# QUES_-1_2.net
KiCad netlist of a schematic drawn in EAGLE
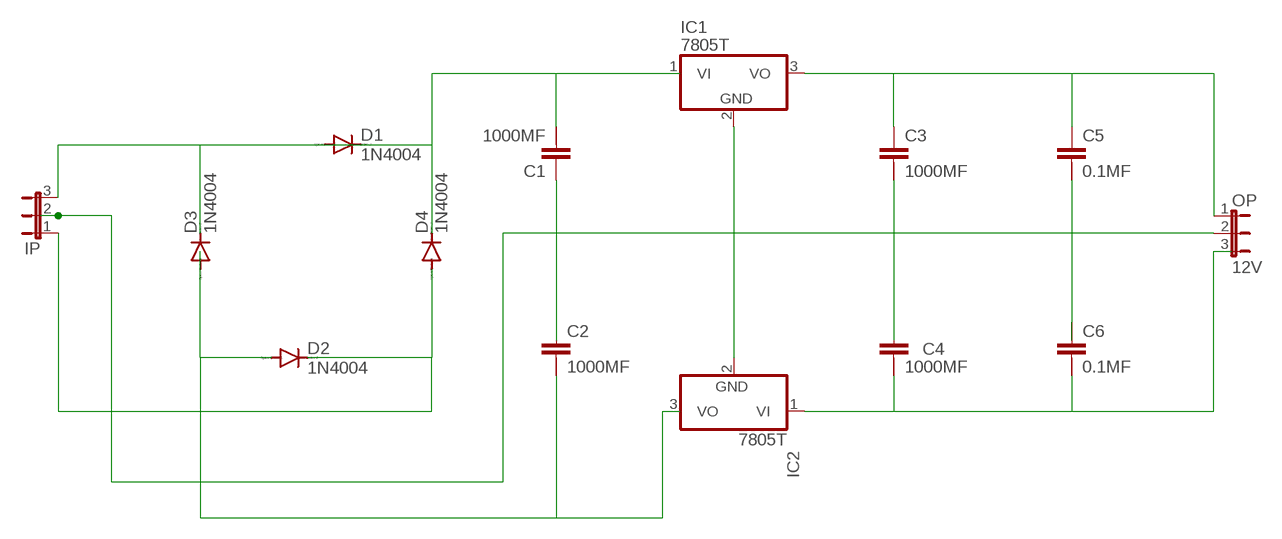
[diagram p0: schematic, sheet 1]

(export (version "E")
  (design (tool "Eeschema 10.0.6"))
  (components
    (comp (ref "C1")
      (value "1000MF")
      (footprint "eagle-import:C2.5_5-2")
      (libsource (lib "eagle-import") (part "C-2.5-5/2"))
    )
    (comp (ref "C2")
      (value "1000MF")
      (footprint "eagle-import:C2.5_5-2")
      (libsource (lib "eagle-import") (part "C-2.5-5/2"))
    )
    (comp (ref "C3")
      (value "1000MF")
      (footprint "eagle-import:C2.5_5-2")
      (libsource (lib "eagle-import") (part "C-2.5-5/2"))
    )
    (comp (ref "C4")
      (value "1000MF")
      (footprint "eagle-import:C2.5_5-2")
      (libsource (lib "eagle-import") (part "C-2.5-5/2"))
    )
    (comp (ref "C5")
      (value "0.1MF")
      (footprint "eagle-import:C2.5_5-2")
      (libsource (lib "eagle-import") (part "C-2.5-5/2"))
    )
    (comp (ref "C6")
      (value "0.1MF")
      (footprint "eagle-import:C2.5_5-2")
      (libsource (lib "eagle-import") (part "C-2.5-5/2"))
    )
    (comp (ref "D1")
      (value "1N4004")
      (footprint "eagle-import:DO41-10")
      (libsource (lib "eagle-import") (part "1N4004"))
    )
    (comp (ref "D2")
      (value "1N4004")
      (footprint "eagle-import:DO41-10")
      (libsource (lib "eagle-import") (part "1N4004"))
    )
    (comp (ref "D3")
      (value "1N4004")
      (footprint "eagle-import:DO41-10")
      (libsource (lib "eagle-import") (part "1N4004"))
    )
    (comp (ref "D4")
      (value "1N4004")
      (footprint "eagle-import:DO41-10")
      (libsource (lib "eagle-import") (part "1N4004"))
    )
    (comp (ref "IC1")
      (value "7805T")
      (footprint "eagle-import:TO220H")
      (libsource (lib "eagle-import") (part "78T05"))
    )
    (comp (ref "IC2")
      (value "7805T")
      (footprint "eagle-import:TO220H")
      (libsource (lib "eagle-import") (part "78T05"))
    )
    (comp (ref "IP")
      (value "JP2E")
      (footprint "eagle-import:JP2")
      (libsource (lib "eagle-import") (part "JP2E"))
    )
    (comp (ref "OP")
      (value "12V")
      (footprint "eagle-import:JP2")
      (libsource (lib "eagle-import") (part "JP2E"))
    )
  )
  (nets
    (net (code "1") (name "Net-(C1-Pad1)") (class "Default")
      (node (ref "C1") (pin "1") (pinfunction "1_1") (pintype "passive"))
      (node (ref "C2") (pin "1") (pinfunction "1_1") (pintype "passive"))
    )
    (net (code "2") (name "Net-(C3-Pad2)") (class "Default")
      (node (ref "C3") (pin "2") (pinfunction "2_2") (pintype "passive"))
      (node (ref "C4") (pin "1") (pinfunction "1_1") (pintype "passive"))
    )
    (net (code "3") (name "Net-(C5-Pad2)") (class "Default")
      (node (ref "C5") (pin "2") (pinfunction "2_2") (pintype "passive"))
      (node (ref "C6") (pin "1") (pinfunction "1_1") (pintype "passive"))
    )
    (net (code "4") (name "Net-(D2-PadC)") (class "Default")
      (node (ref "D2") (pin "C") (pinfunction "C_C") (pintype "passive"))
      (node (ref "D4") (pin "A") (pinfunction "A_A") (pintype "passive"))
      (node (ref "IP") (pin "1") (pinfunction "1_1") (pintype "passive"))
    )
    (net (code "5") (name "Net-(IC1-GND)") (class "Default")
      (node (ref "IC1") (pin "2") (pinfunction "GND_2") (pintype "passive"))
      (node (ref "IC2") (pin "2") (pinfunction "GND_2") (pintype "passive"))
    )
    (net (code "6") (name "Net-(IC1-VI)") (class "Default")
      (node (ref "C1") (pin "2") (pinfunction "2_2") (pintype "passive"))
      (node (ref "D1") (pin "A") (pinfunction "A_A") (pintype "passive"))
      (node (ref "D1") (pin "C") (pinfunction "C_C") (pintype "passive"))
      (node (ref "D3") (pin "C") (pinfunction "C_C") (pintype "passive"))
      (node (ref "D4") (pin "C") (pinfunction "C_C") (pintype "passive"))
      (node (ref "IC1") (pin "1") (pinfunction "VI_1") (pintype "input"))
      (node (ref "IP") (pin "3") (pinfunction "3_3") (pintype "passive"))
    )
    (net (code "7") (name "Net-(IC1-VO)") (class "Default")
      (node (ref "C3") (pin "1") (pinfunction "1_1") (pintype "passive"))
      (node (ref "C5") (pin "1") (pinfunction "1_1") (pintype "passive"))
      (node (ref "IC1") (pin "3") (pinfunction "VO_3") (pintype "passive"))
      (node (ref "OP") (pin "1") (pinfunction "1_1") (pintype "passive"))
    )
    (net (code "8") (name "Net-(IC2-VI)") (class "Default")
      (node (ref "C4") (pin "2") (pinfunction "2_2") (pintype "passive"))
      (node (ref "C6") (pin "2") (pinfunction "2_2") (pintype "passive"))
      (node (ref "IC2") (pin "1") (pinfunction "VI_1") (pintype "input"))
      (node (ref "OP") (pin "3") (pinfunction "3_3") (pintype "passive"))
    )
    (net (code "9") (name "Net-(IC2-VO)") (class "Default")
      (node (ref "C2") (pin "2") (pinfunction "2_2") (pintype "passive"))
      (node (ref "D2") (pin "A") (pinfunction "A_A") (pintype "passive"))
      (node (ref "D3") (pin "A") (pinfunction "A_A") (pintype "passive"))
      (node (ref "IC2") (pin "3") (pinfunction "VO_3") (pintype "passive"))
    )
    (net (code "10") (name "Net-(IP-Pad2)") (class "Default")
      (node (ref "IP") (pin "2") (pinfunction "2_2") (pintype "passive"))
      (node (ref "OP") (pin "2") (pinfunction "2_2") (pintype "passive"))
    )
    (net (code "11") (name "unconnected-(C1-Pad3)") (class "Default")
      (node (ref "C1") (pin "3") (pinfunction "3_3") (pintype "passive"))
    )
    (net (code "12") (name "unconnected-(C2-Pad3)") (class "Default")
      (node (ref "C2") (pin "3") (pinfunction "3_3") (pintype "passive"))
    )
    (net (code "13") (name "unconnected-(C3-Pad3)") (class "Default")
      (node (ref "C3") (pin "3") (pinfunction "3_3") (pintype "passive"))
    )
    (net (code "14") (name "unconnected-(C4-Pad3)") (class "Default")
      (node (ref "C4") (pin "3") (pinfunction "3_3") (pintype "passive"))
    )
    (net (code "15") (name "unconnected-(C5-Pad3)") (class "Default")
      (node (ref "C5") (pin "3") (pinfunction "3_3") (pintype "passive"))
    )
    (net (code "16") (name "unconnected-(C6-Pad3)") (class "Default")
      (node (ref "C6") (pin "3") (pinfunction "3_3") (pintype "passive"))
    )
  )
)
